# SEP00949AG.net
KiCad netlist of a schematic drawn in Altium Designer
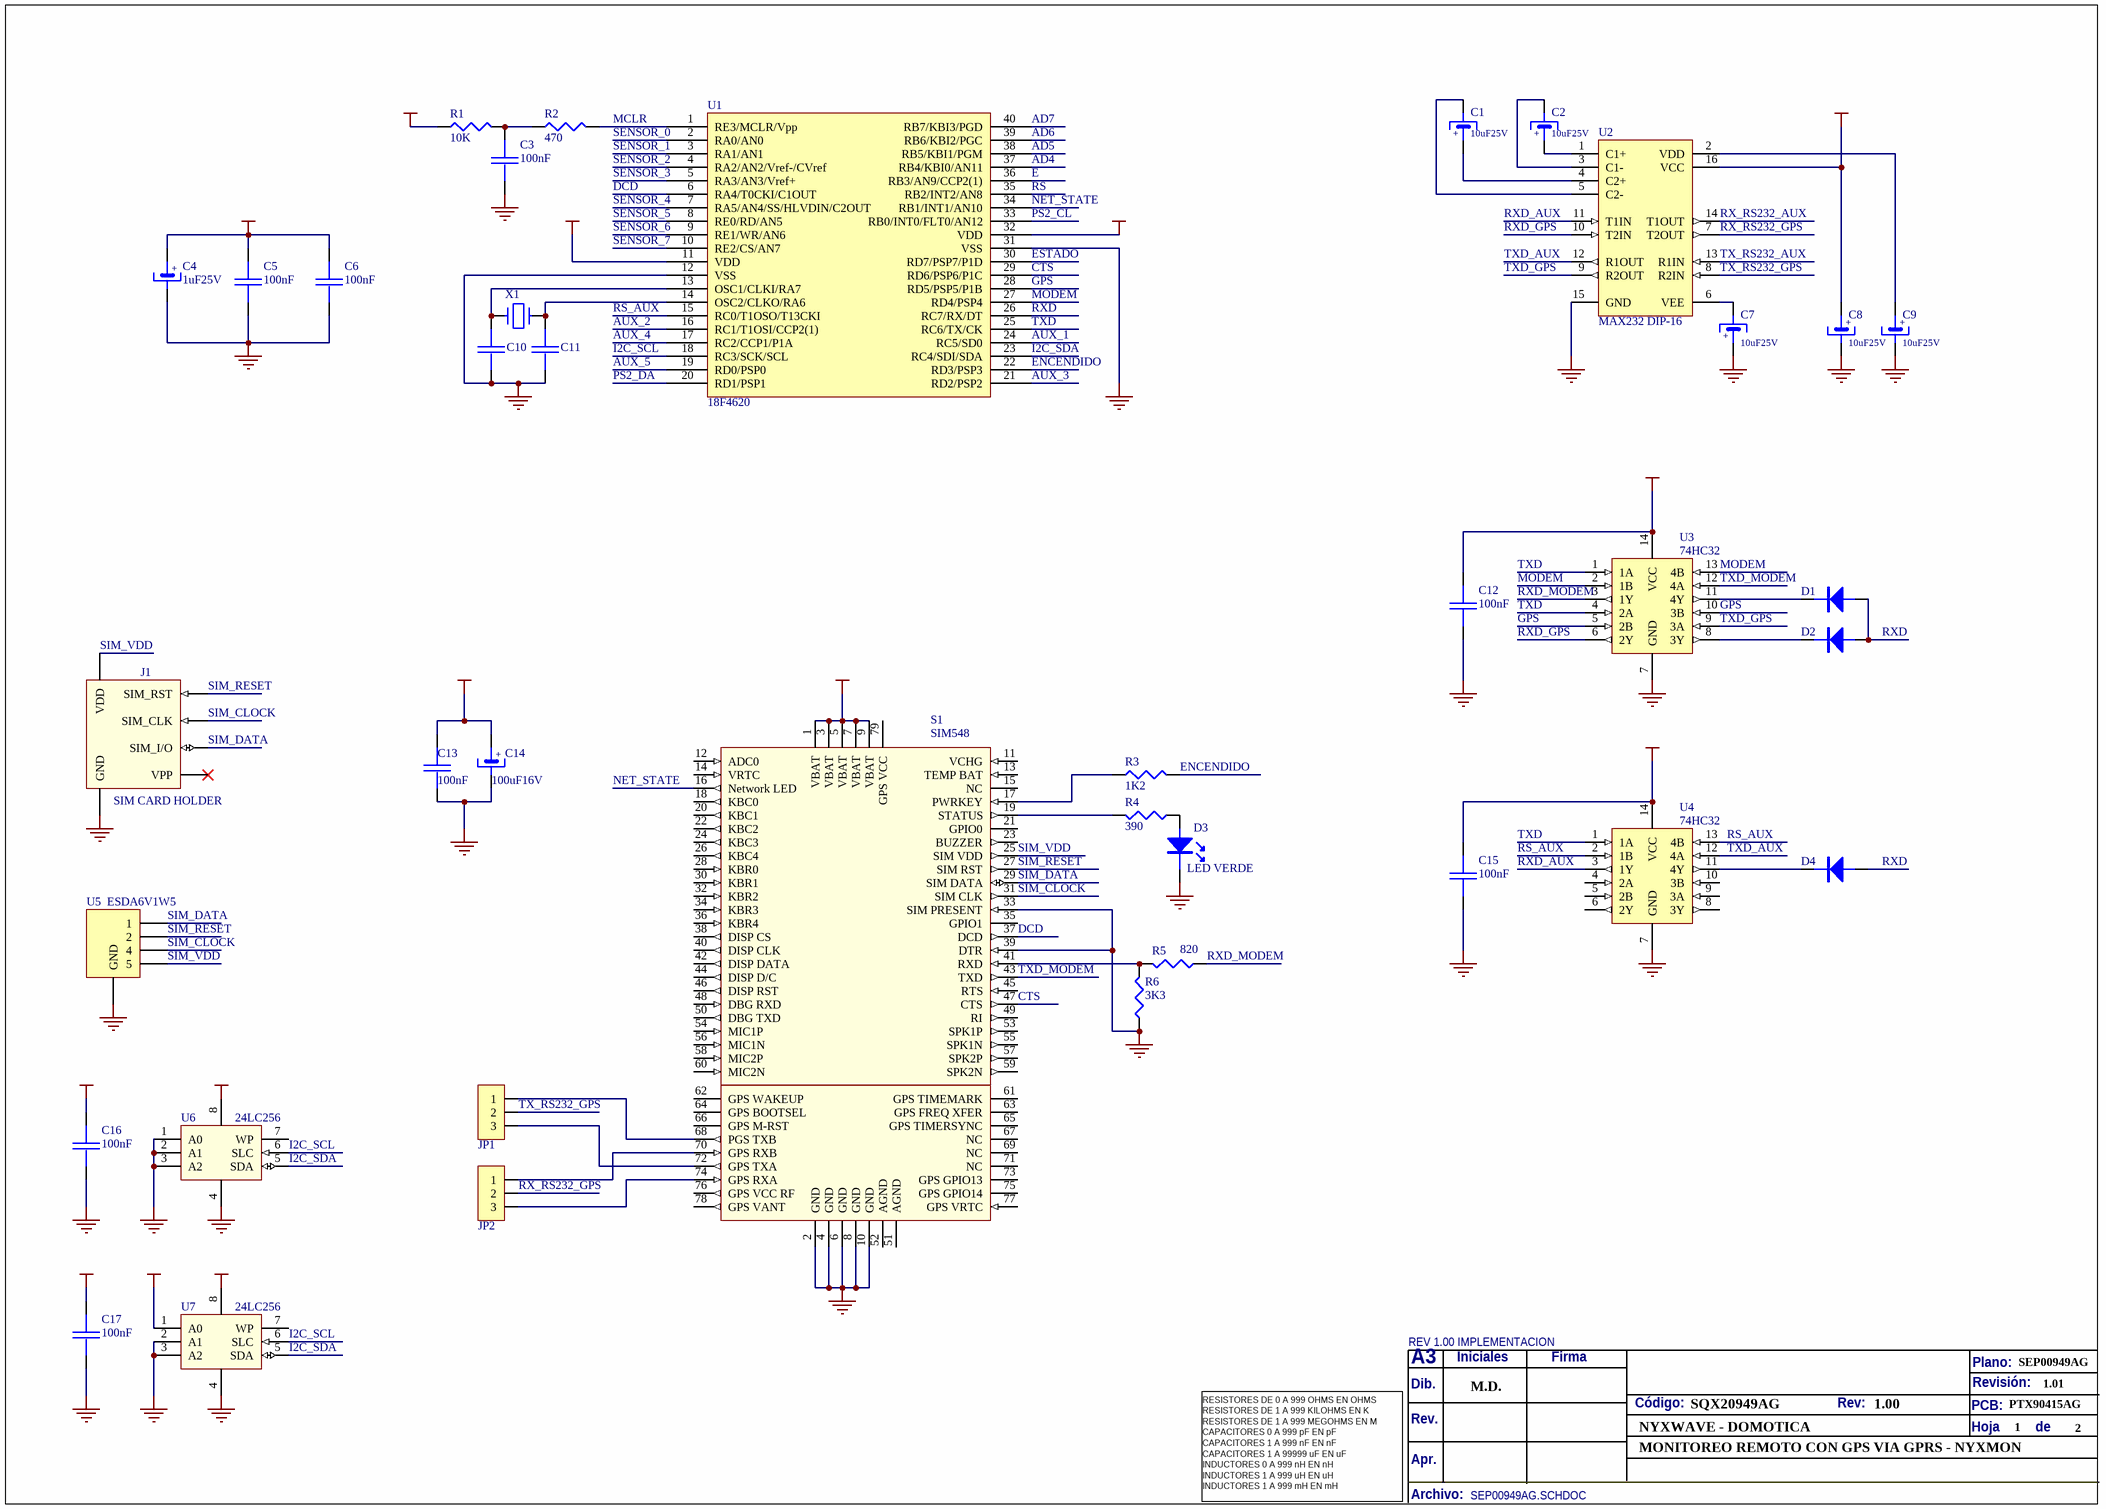
[diagram p0: SEP00949AG.SCHDOC]

(export (version "E")
  (design (tool "Eeschema 10.0.6"))
  (components
    (comp (ref "C1")
      (value "10uF25V")
      (footprint "CE 2.0/5.0")
      (description "CAPACITOR ELECTROLITICO RADIAL 5X11mm PASO 2mm 85ªC +/-20 25V 10uF")
      (libsource (lib "CAPACITORES ELECTROLITICOS") (part "10uF25V 5X11X2"))
    )
    (comp (ref "C2")
      (value "10uF25V")
      (footprint "CE 2.0/5.0")
      (description "CAPACITOR ELECTROLITICO RADIAL 5X11mm PASO 2mm 85ªC +/-20 25V 10uF")
      (libsource (lib "CAPACITORES ELECTROLITICOS") (part "10uF25V 5X11X2"))
    )
    (comp (ref "C3")
      (value "100nF")
      (footprint "0805")
      (description "CAPACITOR SMD 0805 X7R  50 V 100 nF")
      (libsource (lib "CAPACITORES SMD0805") (part "100n"))
    )
    (comp (ref "C4")
      (value "1uF25V")
      (footprint "CE 2.5/5.0")
      (description "CAP ELECT RAD 1.0UF 25V 5X11MM PASO 2MM 85ºC")
      (libsource (lib "CAPACITORES ELECTROLITICOS") (part "1uF25V"))
    )
    (comp (ref "C5")
      (value "100nF")
      (footprint "0805")
      (description "CAPACITOR SMD 0805 X7R  50 V 100 nF")
      (libsource (lib "CAPACITORES SMD0805") (part "100n"))
    )
    (comp (ref "C6")
      (value "100nF")
      (footprint "0805")
      (description "CAPACITOR SMD 0805 X7R  50 V 100 nF")
      (libsource (lib "CAPACITORES SMD0805") (part "100n"))
    )
    (comp (ref "C7")
      (value "10uF25V")
      (footprint "CE 2.0/5.0")
      (description "CAPACITOR ELECTROLITICO RADIAL 5X11mm PASO 2mm 85ªC +/-20 25V 10uF")
      (libsource (lib "CAPACITORES ELECTROLITICOS") (part "10uF25V 5X11X2"))
    )
    (comp (ref "C8")
      (value "10uF25V")
      (footprint "CE 2.0/5.0")
      (description "CAPACITOR ELECTROLITICO RADIAL 5X11mm PASO 2mm 85ªC +/-20 25V 10uF")
      (libsource (lib "CAPACITORES ELECTROLITICOS") (part "10uF25V 5X11X2"))
    )
    (comp (ref "C9")
      (value "10uF25V")
      (footprint "CE 2.0/5.0")
      (description "CAPACITOR ELECTROLITICO RADIAL 5X11mm PASO 2mm 85ªC +/-20 25V 10uF")
      (libsource (lib "CAPACITORES ELECTROLITICOS") (part "10uF25V 5X11X2"))
    )
    (comp (ref "C10")
      (value "15p")
      (footprint "CAP2.54")
      (description "CAPACITOR CERAMICO DISCO 2.54 mm  X7R  50V  15pF")
      (libsource (lib "CAPACITORES CERAMICO DISCO") (part "15p"))
    )
    (comp (ref "C11")
      (value "15p")
      (footprint "CAP2.54")
      (description "CAPACITOR CERAMICO DISCO 2.54 mm  X7R  50V  15pF")
      (libsource (lib "CAPACITORES CERAMICO DISCO") (part "15p"))
    )
    (comp (ref "C12")
      (value "100nF")
      (footprint "0805")
      (description "CAPACITOR SMD 0805 X7R  50 V 100 nF")
      (libsource (lib "CAPACITORES SMD0805") (part "100n"))
    )
    (comp (ref "C13")
      (value "100nF")
      (footprint "0805")
      (description "CAPACITOR SMD 0805 X7R  50 V 100 nF")
      (libsource (lib "CAPACITORES SMD0805") (part "100n"))
    )
    (comp (ref "C14")
      (value "100uF16V")
      (footprint "CE 3.5/8.0")
      (description "CAP ELECT RADIAL 100UF 16V 6.3X12MM PASO 2.5MM 85ºC 20%")
      (libsource (lib "CAPACITORES ELECTROLITICOS") (part "100uF16V"))
    )
    (comp (ref "C15")
      (value "100nF")
      (footprint "0805")
      (description "CAPACITOR SMD 0805 X7R  50 V 100 nF")
      (libsource (lib "CAPACITORES SMD0805") (part "100n"))
    )
    (comp (ref "C16")
      (value "100nF")
      (footprint "0805")
      (description "CAPACITOR SMD 0805 X7R  50 V 100 nF")
      (libsource (lib "CAPACITORES SMD0805") (part "100n"))
    )
    (comp (ref "C17")
      (value "100nF")
      (footprint "0805")
      (description "CAPACITOR SMD 0805 X7R  50 V 100 nF")
      (libsource (lib "CAPACITORES SMD0805") (part "100n"))
    )
    (comp (ref "D1")
      (value "1N4148 DO-35")
      (footprint "DO-35_200")
      (description "1N4148 DO-35 DIODO")
      (libsource (lib "DIODOS") (part "1N4148 DO-35"))
    )
    (comp (ref "D2")
      (value "1N4148 DO-35")
      (footprint "DO-35_200")
      (description "1N4148 DO-35 DIODO")
      (libsource (lib "DIODOS") (part "1N4148 DO-35"))
    )
    (comp (ref "D3")
      (value "LED VERDE")
      (footprint "LED 3MM")
      (description "LED VERDE 3MM")
      (libsource (lib "DIODOS") (part "LED VERDE 3MM"))
    )
    (comp (ref "D4")
      (value "1N4148 DO-35")
      (footprint "DO-35_200")
      (description "1N4148 DO-35 DIODO")
      (libsource (lib "DIODOS") (part "1N4148 DO-35"))
    )
    (comp (ref "J1")
      (value "SIM CARD HOLDER")
      (footprint "SIM CARD HOLDER")
      (description "ZOCALO PARA TARJETA DE MEMORIA SIM")
      (libsource (lib "CONECTORES") (part "SIM CARD HOLDER"))
    )
    (comp (ref "JP1")
      (value "HEADER3")
      (footprint "JUMPER_3")
      (description "TIRA MOLEX 1X40 11MM MACHO RECTA PARA PCB")
      (libsource (lib "CONECTORES") (part "HEADER3"))
    )
    (comp (ref "JP2")
      (value "HEADER3")
      (footprint "JUMPER_3")
      (description "TIRA MOLEX 1X40 11MM MACHO RECTA PARA PCB")
      (libsource (lib "CONECTORES") (part "HEADER3"))
    )
    (comp (ref "R1")
      (value "10K")
      (footprint "RES_MF1/2W_200")
      (description "RESISTOR METAL FILM 0.5 W 5% 10 KILOHMS")
      (libsource (lib "RESISTORES METAL FILM MEDIO WATT") (part "10K"))
    )
    (comp (ref "R2")
      (value "470")
      (footprint "RES_MF1/2W_200")
      (description "RESISTOR METAL FILM 0.5 W 5% 470 OHMS")
      (libsource (lib "RESISTORES METAL FILM MEDIO WATT") (part "470"))
    )
    (comp (ref "R3")
      (value "1K2")
      (footprint "0805")
      (description "RESISTOR SMD0805 0.125 W 5%  1.2 K OHMS")
      (libsource (lib "RESISTORES SMD0805") (part "1K2"))
    )
    (comp (ref "R4")
      (value "390")
      (footprint "RES_MF1/2W_200")
      (description "RESISTOR METAL FILM 0.5 W 5% 390 OHMS")
      (libsource (lib "RESISTORES METAL FILM MEDIO WATT") (part "390"))
    )
    (comp (ref "R5")
      (value "820")
      (footprint "RES_MF1/2W_200")
      (description "RESISTOR METAL FILM 0.5 W 5% 820 OHMS")
      (libsource (lib "RESISTORES METAL FILM MEDIO WATT") (part "820"))
    )
    (comp (ref "R6")
      (value "3K3")
      (footprint "RES_MF1/2W_200")
      (description "RESISTOR METAL FILM 0.5 W 5% 3.3 KILOHMS")
      (libsource (lib "RESISTORES METAL FILM MEDIO WATT") (part "3K3"))
    )
    (comp (ref "S1")
      (value "SIM548")
      (footprint "SIM548")
      (description "SIM340C QUAD-BAND GSM/GPRS GSM850MHz/EGSM900MHz/DCS18000MHz/PCS1900MHz GPS")
      (libsource (lib "SUBCONJUNTOS") (part "SIM548 QUAD-BAND GSM/GPRS GPS"))
    )
    (comp (ref "U1")
      (value "18F4620")
      (footprint "DIP40")
      (description "PIC Microchip")
      (libsource (lib "CIRCUITOS INTEGRADOS DIP") (part "18F4620 P/I"))
    )
    (comp (ref "U2")
      (value "MAX232 DIP-16")
      (footprint "DIP16")
      (description "MAX232 DIP-16 CIRCUITO INTEGRADO")
      (libsource (lib "Maxim Communication Transceiver") (part "MAX232 DIP-16"))
    )
    (comp (ref "U3")
      (value "74HC32")
      (footprint "DIP14")
      (description "74HC08 DIP-14 QUAD 2-INPUT AND GATE")
      (libsource (lib "CIRCUITOS INTEGRADOS DIP") (part "74HC08 DIP"))
    )
    (comp (ref "U4")
      (value "74HC32")
      (footprint "DIP14")
      (description "74HC08 DIP-14 QUAD 2-INPUT AND GATE")
      (libsource (lib "CIRCUITOS INTEGRADOS DIP") (part "74HC08 DIP"))
    )
    (comp (ref "U5")
      (value "ESDA6V1W5")
      (footprint "SOT-323-5L")
      (description "ESDA6V1W5 ARRAY  FOR ESD PROTECTION")
      (libsource (lib "CIRCUITOS INTEGRADOS SMD") (part "ESDA6V1W5"))
    )
    (comp (ref "U6")
      (value "24LC256")
      (footprint "DIP8")
      (description "256K I2C CMOS Serial EEPROM")
      (libsource (lib "CIRCUITOS INTEGRADOS DIP") (part "24LC256"))
    )
    (comp (ref "U7")
      (value "24LC256")
      (footprint "DIP8")
      (description "256K I2C CMOS Serial EEPROM")
      (libsource (lib "CIRCUITOS INTEGRADOS DIP") (part "24LC256"))
    )
    (comp (ref "X1")
      (value "20MHz")
      (footprint "UM5")
      (description "20.000 MHZ XL20M-UM5 10PPM CRISTAL")
      (libsource (lib "*") (part "CRYSTAL"))
    )
  )
  (nets
    (net (code "1") (name "+5V") (class "Default")
      (node (ref "C12") (pin "1") (pintype "passive"))
      (node (ref "C15") (pin "1") (pintype "passive"))
      (node (ref "C16") (pin "2") (pintype "passive"))
      (node (ref "C17") (pin "2") (pintype "passive"))
      (node (ref "C8") (pin "1") (pinfunction "1_1") (pintype "passive"))
      (node (ref "R1") (pin "1") (pintype "passive"))
      (node (ref "U2") (pin "16") (pinfunction "VCC_16") (pintype "power_in"))
      (node (ref "U3") (pin "14") (pinfunction "VCC_14") (pintype "power_in"))
      (node (ref "U4") (pin "14") (pinfunction "VCC_14") (pintype "power_in"))
      (node (ref "U6") (pin "8") (pinfunction "VCC_8") (pintype "power_in"))
      (node (ref "U7") (pin "1") (pinfunction "A0_1") (pintype "passive"))
      (node (ref "U7") (pin "8") (pinfunction "VCC_8") (pintype "power_in"))
    )
    (net (code "6") (name "/AD4") (class "Default")
      (node (ref "U1") (pin "37") (pinfunction "RB4/KBI0/AN11_37") (pintype "passive"))
    )
    (net (code "7") (name "/AD5") (class "Default")
      (node (ref "U1") (pin "38") (pinfunction "RB5/KBI1/PGM_38") (pintype "passive"))
    )
    (net (code "8") (name "/AD6") (class "Default")
      (node (ref "U1") (pin "39") (pinfunction "RB6/KBI2/PGC_39") (pintype "passive"))
    )
    (net (code "9") (name "/AD7") (class "Default")
      (node (ref "U1") (pin "40") (pinfunction "RB7/KBI3/PGD_40") (pintype "passive"))
    )
    (net (code "10") (name "/AUX_1") (class "Default")
      (node (ref "U1") (pin "24") (pinfunction "RC5/SD0_24") (pintype "passive"))
    )
    (net (code "11") (name "/AUX_2") (class "Default")
      (node (ref "U1") (pin "16") (pinfunction "RC1/T1OSI/CCP2(1)_16") (pintype "passive"))
    )
    (net (code "12") (name "/AUX_3") (class "Default")
      (node (ref "U1") (pin "21") (pinfunction "RD2/PSP2_21") (pintype "passive"))
    )
    (net (code "13") (name "/AUX_4") (class "Default")
      (node (ref "U1") (pin "17") (pinfunction "RC2/CCP1/P1A_17") (pintype "passive"))
    )
    (net (code "14") (name "/AUX_5") (class "Default")
      (node (ref "U1") (pin "19") (pinfunction "RD0/PSP0_19") (pintype "passive"))
    )
    (net (code "15") (name "/CTS") (class "Default")
      (node (ref "S1") (pin "47") (pinfunction "CTS_47") (pintype "output"))
      (node (ref "U1") (pin "29") (pinfunction "RD6/PSP6/P1C_29") (pintype "passive"))
    )
    (net (code "16") (name "/DCD") (class "Default")
      (node (ref "S1") (pin "37") (pinfunction "DCD_37") (pintype "output"))
      (node (ref "U1") (pin "6") (pinfunction "RA4/T0CKI/C1OUT_6") (pintype "passive"))
    )
    (net (code "17") (name "/E") (class "Default")
      (node (ref "U1") (pin "36") (pinfunction "RB3/AN9/CCP2(1)_36") (pintype "passive"))
    )
    (net (code "18") (name "/ENCENDIDO") (class "Default")
      (node (ref "R3") (pin "2") (pintype "passive"))
      (node (ref "U1") (pin "22") (pinfunction "RD3/PSP3_22") (pintype "passive"))
    )
    (net (code "19") (name "/ESTADO") (class "Default")
      (node (ref "U1") (pin "30") (pinfunction "RD7/PSP7/P1D_30") (pintype "passive"))
    )
    (net (code "20") (name "/GPS") (class "Default")
      (node (ref "U1") (pin "28") (pinfunction "RD5/PSP5/P1B_28") (pintype "passive"))
      (node (ref "U3") (pin "10") (pinfunction "3B_10") (pintype "input"))
      (node (ref "U3") (pin "5") (pinfunction "2B_5") (pintype "input"))
    )
    (net (code "21") (name "/I2C_SCL") (class "Default")
      (node (ref "U1") (pin "18") (pinfunction "RC3/SCK/SCL_18") (pintype "passive"))
      (node (ref "U6") (pin "6") (pinfunction "SLC_6") (pintype "input"))
      (node (ref "U7") (pin "6") (pinfunction "SLC_6") (pintype "input"))
    )
    (net (code "22") (name "/I2C_SDA") (class "Default")
      (node (ref "U1") (pin "23") (pinfunction "RC4/SDI/SDA_23") (pintype "passive"))
      (node (ref "U6") (pin "5") (pinfunction "SDA_5") (pintype "bidirectional"))
      (node (ref "U7") (pin "5") (pinfunction "SDA_5") (pintype "bidirectional"))
    )
    (net (code "24") (name "/MCLR") (class "Default")
      (node (ref "R2") (pin "2") (pintype "passive"))
      (node (ref "U1") (pin "1") (pinfunction "RE3/MCLR/Vpp_1") (pintype "passive"))
    )
    (net (code "25") (name "/MODEM") (class "Default")
      (node (ref "U1") (pin "27") (pinfunction "RD4/PSP4_27") (pintype "passive"))
      (node (ref "U3") (pin "13") (pinfunction "4B_13") (pintype "input"))
      (node (ref "U3") (pin "2") (pinfunction "1B_2") (pintype "input"))
    )
    (net (code "27") (name "/NET_STATE") (class "Default")
      (node (ref "S1") (pin "16") (pinfunction "Network_LED_16") (pintype "output"))
      (node (ref "U1") (pin "34") (pinfunction "RB1/INT1/AN10_34") (pintype "passive"))
    )
    (net (code "29") (name "/PS2_CL") (class "Default")
      (node (ref "U1") (pin "33") (pinfunction "RB0/INT0/FLT0/AN12_33") (pintype "passive"))
    )
    (net (code "30") (name "/PS2_DA") (class "Default")
      (node (ref "U1") (pin "20") (pinfunction "RD1/PSP1_20") (pintype "passive"))
    )
    (net (code "32") (name "/RS") (class "Default")
      (node (ref "U1") (pin "35") (pinfunction "RB2/INT2/AN8_35") (pintype "passive"))
    )
    (net (code "33") (name "/RS_AUX") (class "Default")
      (node (ref "U1") (pin "15") (pinfunction "RC0/T1OSO/T13CKI_15") (pintype "passive"))
      (node (ref "U4") (pin "13") (pinfunction "4B_13") (pintype "input"))
      (node (ref "U4") (pin "2") (pinfunction "1B_2") (pintype "input"))
    )
    (net (code "34") (name "/RXD") (class "Default")
      (node (ref "D1") (pin "A") (pinfunction "A_A") (pintype "passive"))
      (node (ref "D2") (pin "A") (pinfunction "A_A") (pintype "passive"))
      (node (ref "D4") (pin "A") (pinfunction "A_A") (pintype "passive"))
      (node (ref "U1") (pin "26") (pinfunction "RC7/RX/DT_26") (pintype "passive"))
    )
    (net (code "35") (name "/RXD_AUX") (class "Default")
      (node (ref "U2") (pin "11") (pinfunction "T1IN_11") (pintype "input"))
      (node (ref "U4") (pin "3") (pinfunction "1Y_3") (pintype "output"))
    )
    (net (code "36") (name "/RXD_GPS") (class "Default")
      (node (ref "U2") (pin "10") (pinfunction "T2IN_10") (pintype "input"))
      (node (ref "U3") (pin "6") (pinfunction "2Y_6") (pintype "output"))
    )
    (net (code "37") (name "/RXD_MODEM") (class "Default")
      (node (ref "R5") (pin "1") (pintype "passive"))
      (node (ref "U3") (pin "3") (pinfunction "1Y_3") (pintype "output"))
    )
    (net (code "38") (name "/RX_RS232_AUX") (class "Default")
      (node (ref "U2") (pin "14") (pinfunction "T1OUT_14") (pintype "output"))
    )
    (net (code "39") (name "/RX_RS232_GPS") (class "Default")
      (node (ref "JP2") (pin "2") (pinfunction "2_2") (pintype "passive"))
      (node (ref "U2") (pin "7") (pinfunction "T2OUT_7") (pintype "output"))
    )
    (net (code "40") (name "/SENSOR_0") (class "Default")
      (node (ref "U1") (pin "2") (pinfunction "RA0/AN0_2") (pintype "passive"))
    )
    (net (code "41") (name "/SENSOR_1") (class "Default")
      (node (ref "U1") (pin "3") (pinfunction "RA1/AN1_3") (pintype "passive"))
    )
    (net (code "42") (name "/SENSOR_2") (class "Default")
      (node (ref "U1") (pin "4") (pinfunction "RA2/AN2/Vref-/CVref_4") (pintype "passive"))
    )
    (net (code "43") (name "/SENSOR_3") (class "Default")
      (node (ref "U1") (pin "5") (pinfunction "RA3/AN3/Vref+_5") (pintype "passive"))
    )
    (net (code "44") (name "/SENSOR_4") (class "Default")
      (node (ref "U1") (pin "7") (pinfunction "RA5/AN4/SS/HLVDIN/C2OUT_7") (pintype "passive"))
    )
    (net (code "45") (name "/SENSOR_5") (class "Default")
      (node (ref "U1") (pin "8") (pinfunction "RE0/RD/AN5_8") (pintype "passive"))
    )
    (net (code "46") (name "/SENSOR_6") (class "Default")
      (node (ref "U1") (pin "9") (pinfunction "RE1/WR/AN6_9") (pintype "passive"))
    )
    (net (code "47") (name "/SENSOR_7") (class "Default")
      (node (ref "U1") (pin "10") (pinfunction "RE2/CS/AN7_10") (pintype "passive"))
    )
    (net (code "49") (name "/SIM_CLOCK") (class "Default")
      (node (ref "J1") (pin "3") (pinfunction "SIM_CLK_3") (pintype "input"))
      (node (ref "S1") (pin "31") (pinfunction "SIM_CLK_31") (pintype "output"))
      (node (ref "U5") (pin "4") (pinfunction "4_4") (pintype "passive"))
    )
    (net (code "50") (name "/SIM_DATA") (class "Default")
      (node (ref "J1") (pin "6") (pinfunction "SIM_I/O_6") (pintype "bidirectional"))
      (node (ref "S1") (pin "29") (pinfunction "SIM_DATA_29") (pintype "bidirectional"))
      (node (ref "U5") (pin "1") (pinfunction "1_1") (pintype "passive"))
    )
    (net (code "51") (name "/SIM_RESET") (class "Default")
      (node (ref "J1") (pin "2") (pinfunction "SIM_RST_2") (pintype "input"))
      (node (ref "S1") (pin "27") (pinfunction "SIM_RST_27") (pintype "output"))
      (node (ref "U5") (pin "2") (pinfunction "2_2") (pintype "passive"))
    )
    (net (code "52") (name "/SIM_VDD") (class "Default")
      (node (ref "J1") (pin "1") (pinfunction "VDD_1") (pintype "power_in"))
      (node (ref "S1") (pin "25") (pinfunction "SIM_VDD_25") (pintype "output"))
      (node (ref "U5") (pin "5") (pinfunction "5_5") (pintype "passive"))
    )
    (net (code "54") (name "/TXD") (class "Default")
      (node (ref "U1") (pin "25") (pinfunction "RC6/TX/CK_25") (pintype "passive"))
      (node (ref "U3") (pin "1") (pinfunction "1A_1") (pintype "input"))
      (node (ref "U3") (pin "4") (pinfunction "2A_4") (pintype "input"))
      (node (ref "U4") (pin "1") (pinfunction "1A_1") (pintype "input"))
    )
    (net (code "55") (name "/TXD_AUX") (class "Default")
      (node (ref "U2") (pin "12") (pinfunction "R1OUT_12") (pintype "output"))
      (node (ref "U4") (pin "12") (pinfunction "4A_12") (pintype "input"))
    )
    (net (code "56") (name "/TXD_GPS") (class "Default")
      (node (ref "U2") (pin "9") (pinfunction "R2OUT_9") (pintype "output"))
      (node (ref "U3") (pin "9") (pinfunction "3A_9") (pintype "input"))
    )
    (net (code "57") (name "/TXD_MODEM") (class "Default")
      (node (ref "S1") (pin "43") (pinfunction "TXD_43") (pintype "output"))
      (node (ref "U3") (pin "12") (pinfunction "4A_12") (pintype "input"))
    )
    (net (code "58") (name "/TX_RS232_AUX") (class "Default")
      (node (ref "U2") (pin "13") (pinfunction "R1IN_13") (pintype "input"))
    )
    (net (code "59") (name "/TX_RS232_GPS") (class "Default")
      (node (ref "JP1") (pin "2") (pinfunction "2_2") (pintype "passive"))
      (node (ref "U2") (pin "8") (pinfunction "R2IN_8") (pintype "input"))
    )
    (net (code "60") (name "GND") (class "Default")
      (node (ref "C10") (pin "1") (pintype "passive"))
      (node (ref "C11") (pin "1") (pintype "passive"))
      (node (ref "C12") (pin "2") (pintype "passive"))
      (node (ref "C13") (pin "1") (pintype "passive"))
      (node (ref "C14") (pin "2") (pinfunction "2_2") (pintype "passive"))
      (node (ref "C15") (pin "2") (pintype "passive"))
      (node (ref "C16") (pin "1") (pintype "passive"))
      (node (ref "C17") (pin "1") (pintype "passive"))
      (node (ref "C3") (pin "1") (pintype "passive"))
      (node (ref "C4") (pin "2") (pinfunction "2_2") (pintype "passive"))
      (node (ref "C5") (pin "2") (pintype "passive"))
      (node (ref "C6") (pin "1") (pintype "passive"))
      (node (ref "C7") (pin "1") (pinfunction "1_1") (pintype "passive"))
      (node (ref "C8") (pin "2") (pinfunction "2_2") (pintype "passive"))
      (node (ref "C9") (pin "2") (pinfunction "2_2") (pintype "passive"))
      (node (ref "D3") (pin "K") (pinfunction "K_K") (pintype "passive"))
      (node (ref "J1") (pin "4") (pinfunction "GND_4") (pintype "passive"))
      (node (ref "R6") (pin "1") (pintype "passive"))
      (node (ref "S1") (pin "10") (pinfunction "GND_10") (pintype "passive"))
      (node (ref "S1") (pin "2") (pinfunction "GND_2") (pintype "passive"))
      (node (ref "S1") (pin "33") (pinfunction "SIM_PRESENT_33") (pintype "input"))
      (node (ref "S1") (pin "39") (pinfunction "DTR_39") (pintype "input"))
      (node (ref "S1") (pin "4") (pinfunction "GND_4") (pintype "passive"))
      (node (ref "S1") (pin "6") (pinfunction "GND_6") (pintype "passive"))
      (node (ref "S1") (pin "8") (pinfunction "GND_8") (pintype "passive"))
      (node (ref "U1") (pin "12") (pinfunction "VSS_12") (pintype "passive"))
      (node (ref "U1") (pin "31") (pinfunction "VSS_31") (pintype "passive"))
      (node (ref "U2") (pin "15") (pinfunction "GND_15") (pintype "power_in"))
      (node (ref "U3") (pin "7") (pinfunction "GND_7") (pintype "power_in"))
      (node (ref "U4") (pin "7") (pinfunction "GND_7") (pintype "power_in"))
      (node (ref "U5") (pin "3") (pinfunction "GND_3") (pintype "passive"))
      (node (ref "U6") (pin "1") (pinfunction "A0_1") (pintype "passive"))
      (node (ref "U6") (pin "2") (pinfunction "A1_2") (pintype "passive"))
      (node (ref "U6") (pin "3") (pinfunction "A2_3") (pintype "passive"))
      (node (ref "U6") (pin "4") (pinfunction "VSS_4") (pintype "passive"))
      (node (ref "U7") (pin "2") (pinfunction "A1_2") (pintype "passive"))
      (node (ref "U7") (pin "3") (pinfunction "A2_3") (pintype "passive"))
      (node (ref "U7") (pin "4") (pinfunction "VSS_4") (pintype "passive"))
    )
    (net (code "61") (name "Net-(C3-Pad2)") (class "Default")
      (node (ref "C3") (pin "2") (pintype "passive"))
      (node (ref "R1") (pin "2") (pintype "passive"))
      (node (ref "R2") (pin "1") (pintype "passive"))
    )
    (net (code "62") (name "Net-(D3-PadA)") (class "Default")
      (node (ref "D3") (pin "A") (pinfunction "A_A") (pintype "passive"))
      (node (ref "R4") (pin "1") (pintype "passive"))
    )
    (net (code "63") (name "Net-(S1-GPS_RXA)") (class "Default")
      (node (ref "JP2") (pin "3") (pinfunction "3_3") (pintype "passive"))
      (node (ref "S1") (pin "74") (pinfunction "GPS_RXA_74") (pintype "input"))
    )
    (net (code "64") (name "Net-(S1-GPS_RXB)") (class "Default")
      (node (ref "JP2") (pin "1") (pinfunction "1_1") (pintype "passive"))
      (node (ref "S1") (pin "70") (pinfunction "GPS_RXB_70") (pintype "input"))
    )
    (net (code "65") (name "Net-(S1-GPS_TXA)") (class "Default")
      (node (ref "JP1") (pin "3") (pinfunction "3_3") (pintype "passive"))
      (node (ref "S1") (pin "72") (pinfunction "GPS_TXA_72") (pintype "output"))
    )
    (net (code "66") (name "Net-(S1-PGS_TXB)") (class "Default")
      (node (ref "JP1") (pin "1") (pinfunction "1_1") (pintype "passive"))
      (node (ref "S1") (pin "68") (pinfunction "PGS_TXB_68") (pintype "output"))
    )
    (net (code "67") (name "Net-(S1-PWRKEY)") (class "Default")
      (node (ref "R3") (pin "1") (pintype "passive"))
      (node (ref "S1") (pin "17") (pinfunction "PWRKEY_17") (pintype "input"))
    )
    (net (code "68") (name "Net-(S1-RXD)") (class "Default")
      (node (ref "R5") (pin "2") (pintype "passive"))
      (node (ref "R6") (pin "2") (pintype "passive"))
      (node (ref "S1") (pin "41") (pinfunction "RXD_41") (pintype "input"))
    )
    (net (code "69") (name "Net-(S1-STATUS)") (class "Default")
      (node (ref "R4") (pin "2") (pintype "passive"))
      (node (ref "S1") (pin "19") (pinfunction "STATUS_19") (pintype "output"))
    )
    (net (code "70") (name "Net-(U1-OSC1{slash}CLKI{slash}RA7)") (class "Default")
      (node (ref "C10") (pin "2") (pintype "passive"))
      (node (ref "U1") (pin "13") (pinfunction "OSC1/CLKI/RA7_13") (pintype "passive"))
      (node (ref "X1") (pin "2") (pintype "passive"))
    )
    (net (code "71") (name "Net-(U1-OSC2{slash}CLKO{slash}RA6)") (class "Default")
      (node (ref "C11") (pin "2") (pintype "passive"))
      (node (ref "U1") (pin "14") (pinfunction "OSC2/CLKO/RA6_14") (pintype "passive"))
      (node (ref "X1") (pin "1") (pintype "passive"))
    )
    (net (code "72") (name "Net-(U2-C1+)") (class "Default")
      (node (ref "C2") (pin "1") (pinfunction "1_1") (pintype "passive"))
      (node (ref "U2") (pin "1") (pinfunction "C1+_1") (pintype "passive"))
    )
    (net (code "73") (name "Net-(U2-C1-)") (class "Default")
      (node (ref "C2") (pin "2") (pinfunction "2_2") (pintype "passive"))
      (node (ref "U2") (pin "3") (pinfunction "C1-_3") (pintype "passive"))
    )
    (net (code "74") (name "Net-(U2-C2+)") (class "Default")
      (node (ref "C1") (pin "1") (pinfunction "1_1") (pintype "passive"))
      (node (ref "U2") (pin "4") (pinfunction "C2+_4") (pintype "passive"))
    )
    (net (code "75") (name "Net-(U2-C2-)") (class "Default")
      (node (ref "C1") (pin "2") (pinfunction "2_2") (pintype "passive"))
      (node (ref "U2") (pin "5") (pinfunction "C2-_5") (pintype "passive"))
    )
    (net (code "76") (name "Net-(U2-VDD)") (class "Default")
      (node (ref "C9") (pin "1") (pinfunction "1_1") (pintype "passive"))
      (node (ref "U2") (pin "2") (pinfunction "VDD_2") (pintype "power_in"))
    )
    (net (code "77") (name "Net-(U2-VEE)") (class "Default")
      (node (ref "C7") (pin "2") (pinfunction "2_2") (pintype "passive"))
      (node (ref "U2") (pin "6") (pinfunction "VEE_6") (pintype "power_in"))
    )
    (net (code "78") (name "Net-(U3-3Y)") (class "Default")
      (node (ref "D2") (pin "K") (pinfunction "K_K") (pintype "passive"))
      (node (ref "U3") (pin "8") (pinfunction "3Y_8") (pintype "output"))
    )
    (net (code "79") (name "Net-(U3-4Y)") (class "Default")
      (node (ref "D1") (pin "K") (pinfunction "K_K") (pintype "passive"))
      (node (ref "U3") (pin "11") (pinfunction "4Y_11") (pintype "output"))
    )
    (net (code "80") (name "Net-(U4-4Y)") (class "Default")
      (node (ref "D4") (pin "K") (pinfunction "K_K") (pintype "passive"))
      (node (ref "U4") (pin "11") (pinfunction "4Y_11") (pintype "output"))
    )
    (net (code "81") (name "VBAT") (class "Default")
      (node (ref "C13") (pin "2") (pintype "passive"))
      (node (ref "C14") (pin "1") (pinfunction "1_1") (pintype "passive"))
      (node (ref "S1") (pin "1") (pinfunction "VBAT_1") (pintype "power_in"))
      (node (ref "S1") (pin "3") (pinfunction "VBAT_3") (pintype "power_in"))
      (node (ref "S1") (pin "5") (pinfunction "VBAT_5") (pintype "power_in"))
      (node (ref "S1") (pin "7") (pinfunction "VBAT_7") (pintype "power_in"))
      (node (ref "S1") (pin "9") (pinfunction "VBAT_9") (pintype "power_in"))
    )
    (net (code "82") (name "VDD") (class "Default")
      (node (ref "C4") (pin "1") (pinfunction "1_1") (pintype "passive"))
      (node (ref "C5") (pin "1") (pintype "passive"))
      (node (ref "C6") (pin "2") (pintype "passive"))
      (node (ref "U1") (pin "11") (pinfunction "VDD_11") (pintype "passive"))
      (node (ref "U1") (pin "32") (pinfunction "VDD_32") (pintype "passive"))
    )
    (net (code "83") (name "unconnected-(J1-VPP-Pad5)") (class "Default")
      (node (ref "J1") (pin "5") (pinfunction "VPP_5") (pintype "passive+no_connect"))
    )
    (net (code "84") (name "unconnected-(S1-ADC0-Pad12)") (class "Default")
      (node (ref "S1") (pin "12") (pinfunction "ADC0_12") (pintype "input"))
    )
    (net (code "85") (name "unconnected-(S1-AGND-Pad51)") (class "Default")
      (node (ref "S1") (pin "51") (pinfunction "AGND_51") (pintype "passive"))
    )
    (net (code "86") (name "unconnected-(S1-AGND-Pad52)") (class "Default")
      (node (ref "S1") (pin "52") (pinfunction "AGND_52") (pintype "passive"))
    )
    (net (code "87") (name "unconnected-(S1-BUZZER-Pad23)") (class "Default")
      (node (ref "S1") (pin "23") (pinfunction "BUZZER_23") (pintype "output"))
    )
    (net (code "88") (name "unconnected-(S1-DBG_RXD-Pad48)") (class "Default")
      (node (ref "S1") (pin "48") (pinfunction "DBG_RXD_48") (pintype "input"))
    )
    (net (code "89") (name "unconnected-(S1-DBG_TXD-Pad50)") (class "Default")
      (node (ref "S1") (pin "50") (pinfunction "DBG_TXD_50") (pintype "output"))
    )
    (net (code "90") (name "unconnected-(S1-DISP_CLK-Pad40)") (class "Default")
      (node (ref "S1") (pin "40") (pinfunction "DISP_CLK_40") (pintype "output"))
    )
    (net (code "91") (name "unconnected-(S1-DISP_CS-Pad38)") (class "Default")
      (node (ref "S1") (pin "38") (pinfunction "DISP_CS_38") (pintype "output"))
    )
    (net (code "92") (name "unconnected-(S1-DISP_DATA-Pad42)") (class "Default")
      (node (ref "S1") (pin "42") (pinfunction "DISP_DATA_42") (pintype "output"))
    )
    (net (code "93") (name "unconnected-(S1-DISP_D{slash}C-Pad44)") (class "Default")
      (node (ref "S1") (pin "44") (pinfunction "DISP_D/C_44") (pintype "output"))
    )
    (net (code "94") (name "unconnected-(S1-DISP_RST-Pad46)") (class "Default")
      (node (ref "S1") (pin "46") (pinfunction "DISP_RST_46") (pintype "output"))
    )
    (net (code "95") (name "unconnected-(S1-GPIO0-Pad21)") (class "Default")
      (node (ref "S1") (pin "21") (pinfunction "GPIO0_21") (pintype "passive"))
    )
    (net (code "96") (name "unconnected-(S1-GPIO1-Pad35)") (class "Default")
      (node (ref "S1") (pin "35") (pinfunction "GPIO1_35") (pintype "passive"))
    )
    (net (code "97") (name "unconnected-(S1-GPS_BOOTSEL-Pad64)") (class "Default")
      (node (ref "S1") (pin "64") (pinfunction "GPS_BOOTSEL_64") (pintype "passive"))
    )
    (net (code "98") (name "unconnected-(S1-GPS_FREQ_XFER-Pad63)") (class "Default")
      (node (ref "S1") (pin "63") (pinfunction "GPS_FREQ_XFER_63") (pintype "passive"))
    )
    (net (code "99") (name "unconnected-(S1-GPS_GPIO13-Pad73)") (class "Default")
      (node (ref "S1") (pin "73") (pinfunction "GPS_GPIO13_73") (pintype "passive"))
    )
    (net (code "100") (name "unconnected-(S1-GPS_GPIO14-Pad75)") (class "Default")
      (node (ref "S1") (pin "75") (pinfunction "GPS_GPIO14_75") (pintype "passive"))
    )
    (net (code "101") (name "unconnected-(S1-GPS_M-RST-Pad66)") (class "Default")
      (node (ref "S1") (pin "66") (pinfunction "GPS_M-RST_66") (pintype "passive"))
    )
    (net (code "102") (name "unconnected-(S1-GPS_TIMEMARK-Pad61)") (class "Default")
      (node (ref "S1") (pin "61") (pinfunction "GPS_TIMEMARK_61") (pintype "passive"))
    )
    (net (code "103") (name "unconnected-(S1-GPS_TIMERSYNC-Pad65)") (class "Default")
      (node (ref "S1") (pin "65") (pinfunction "GPS_TIMERSYNC_65") (pintype "passive"))
    )
    (net (code "104") (name "unconnected-(S1-GPS_VANT-Pad78)") (class "Default")
      (node (ref "S1") (pin "78") (pinfunction "GPS_VANT_78") (pintype "output"))
    )
    (net (code "105") (name "unconnected-(S1-GPS_VCC-Pad79)") (class "Default")
      (node (ref "S1") (pin "79") (pinfunction "GPS_VCC_79") (pintype "power_in"))
    )
    (net (code "106") (name "unconnected-(S1-GPS_VCC_RF-Pad76)") (class "Default")
      (node (ref "S1") (pin "76") (pinfunction "GPS_VCC_RF_76") (pintype "output"))
    )
    (net (code "107") (name "unconnected-(S1-GPS_VRTC-Pad77)") (class "Default")
      (node (ref "S1") (pin "77") (pinfunction "GPS_VRTC_77") (pintype "input"))
    )
    (net (code "108") (name "unconnected-(S1-GPS_WAKEUP-Pad62)") (class "Default")
      (node (ref "S1") (pin "62") (pinfunction "GPS_WAKEUP_62") (pintype "passive"))
    )
    (net (code "109") (name "unconnected-(S1-KBC0-Pad18)") (class "Default")
      (node (ref "S1") (pin "18") (pinfunction "KBC0_18") (pintype "output"))
    )
    (net (code "110") (name "unconnected-(S1-KBC1-Pad20)") (class "Default")
      (node (ref "S1") (pin "20") (pinfunction "KBC1_20") (pintype "output"))
    )
    (net (code "111") (name "unconnected-(S1-KBC2-Pad22)") (class "Default")
      (node (ref "S1") (pin "22") (pinfunction "KBC2_22") (pintype "output"))
    )
    (net (code "112") (name "unconnected-(S1-KBC3-Pad24)") (class "Default")
      (node (ref "S1") (pin "24") (pinfunction "KBC3_24") (pintype "output"))
    )
    (net (code "113") (name "unconnected-(S1-KBC4-Pad26)") (class "Default")
      (node (ref "S1") (pin "26") (pinfunction "KBC4_26") (pintype "output"))
    )
    (net (code "114") (name "unconnected-(S1-KBR0-Pad28)") (class "Default")
      (node (ref "S1") (pin "28") (pinfunction "KBR0_28") (pintype "input"))
    )
    (net (code "115") (name "unconnected-(S1-KBR1-Pad30)") (class "Default")
      (node (ref "S1") (pin "30") (pinfunction "KBR1_30") (pintype "input"))
    )
    (net (code "116") (name "unconnected-(S1-KBR2-Pad32)") (class "Default")
      (node (ref "S1") (pin "32") (pinfunction "KBR2_32") (pintype "input"))
    )
    (net (code "117") (name "unconnected-(S1-KBR3-Pad34)") (class "Default")
      (node (ref "S1") (pin "34") (pinfunction "KBR3_34") (pintype "input"))
    )
    (net (code "118") (name "unconnected-(S1-KBR4-Pad36)") (class "Default")
      (node (ref "S1") (pin "36") (pinfunction "KBR4_36") (pintype "input"))
    )
    (net (code "119") (name "unconnected-(S1-MIC1N-Pad56)") (class "Default")
      (node (ref "S1") (pin "56") (pinfunction "MIC1N_56") (pintype "input"))
    )
    (net (code "120") (name "unconnected-(S1-MIC1P-Pad54)") (class "Default")
      (node (ref "S1") (pin "54") (pinfunction "MIC1P_54") (pintype "input"))
    )
    (net (code "121") (name "unconnected-(S1-MIC2N-Pad60)") (class "Default")
      (node (ref "S1") (pin "60") (pinfunction "MIC2N_60") (pintype "input"))
    )
    (net (code "122") (name "unconnected-(S1-MIC2P-Pad58)") (class "Default")
      (node (ref "S1") (pin "58") (pinfunction "MIC2P_58") (pintype "input"))
    )
    (net (code "123") (name "unconnected-(S1-NC-Pad15)") (class "Default")
      (node (ref "S1") (pin "15") (pinfunction "NC_15") (pintype "passive"))
    )
    (net (code "124") (name "unconnected-(S1-NC-Pad67)") (class "Default")
      (node (ref "S1") (pin "67") (pinfunction "NC_67") (pintype "passive"))
    )
    (net (code "125") (name "unconnected-(S1-NC-Pad69)") (class "Default")
      (node (ref "S1") (pin "69") (pinfunction "NC_69") (pintype "passive"))
    )
    (net (code "126") (name "unconnected-(S1-NC-Pad71)") (class "Default")
      (node (ref "S1") (pin "71") (pinfunction "NC_71") (pintype "passive"))
    )
    (net (code "127") (name "unconnected-(S1-RI-Pad49)") (class "Default")
      (node (ref "S1") (pin "49") (pinfunction "RI_49") (pintype "output"))
    )
    (net (code "128") (name "unconnected-(S1-RTS-Pad45)") (class "Default")
      (node (ref "S1") (pin "45") (pinfunction "RTS_45") (pintype "input"))
    )
    (net (code "129") (name "unconnected-(S1-SPK1N-Pad55)") (class "Default")
      (node (ref "S1") (pin "55") (pinfunction "SPK1N_55") (pintype "output"))
    )
    (net (code "130") (name "unconnected-(S1-SPK1P-Pad53)") (class "Default")
      (node (ref "S1") (pin "53") (pinfunction "SPK1P_53") (pintype "output"))
    )
    (net (code "131") (name "unconnected-(S1-SPK2N-Pad59)") (class "Default")
      (node (ref "S1") (pin "59") (pinfunction "SPK2N_59") (pintype "output"))
    )
    (net (code "132") (name "unconnected-(S1-SPK2P-Pad57)") (class "Default")
      (node (ref "S1") (pin "57") (pinfunction "SPK2P_57") (pintype "output"))
    )
    (net (code "133") (name "unconnected-(S1-TEMP_BAT-Pad13)") (class "Default")
      (node (ref "S1") (pin "13") (pinfunction "TEMP_BAT_13") (pintype "input"))
    )
    (net (code "134") (name "unconnected-(S1-VCHG-Pad11)") (class "Default")
      (node (ref "S1") (pin "11") (pinfunction "VCHG_11") (pintype "input"))
    )
    (net (code "135") (name "unconnected-(S1-VRTC-Pad14)") (class "Default")
      (node (ref "S1") (pin "14") (pinfunction "VRTC_14") (pintype "input"))
    )
    (net (code "136") (name "unconnected-(U4-2A-Pad4)") (class "Default")
      (node (ref "U4") (pin "4") (pinfunction "2A_4") (pintype "input"))
    )
    (net (code "137") (name "unconnected-(U4-2B-Pad5)") (class "Default")
      (node (ref "U4") (pin "5") (pinfunction "2B_5") (pintype "input"))
    )
    (net (code "138") (name "unconnected-(U4-2Y-Pad6)") (class "Default")
      (node (ref "U4") (pin "6") (pinfunction "2Y_6") (pintype "output"))
    )
    (net (code "139") (name "unconnected-(U4-3A-Pad9)") (class "Default")
      (node (ref "U4") (pin "9") (pinfunction "3A_9") (pintype "input"))
    )
    (net (code "140") (name "unconnected-(U4-3B-Pad10)") (class "Default")
      (node (ref "U4") (pin "10") (pinfunction "3B_10") (pintype "input"))
    )
    (net (code "141") (name "unconnected-(U4-3Y-Pad8)") (class "Default")
      (node (ref "U4") (pin "8") (pinfunction "3Y_8") (pintype "output"))
    )
    (net (code "142") (name "unconnected-(U6-WP-Pad7)") (class "Default")
      (node (ref "U6") (pin "7") (pinfunction "WP_7") (pintype "passive"))
    )
    (net (code "143") (name "unconnected-(U7-WP-Pad7)") (class "Default")
      (node (ref "U7") (pin "7") (pinfunction "WP_7") (pintype "passive"))
    )
  )
)
